# rigidPCB.net
KiCad netlist of a schematic drawn in Altium Designer
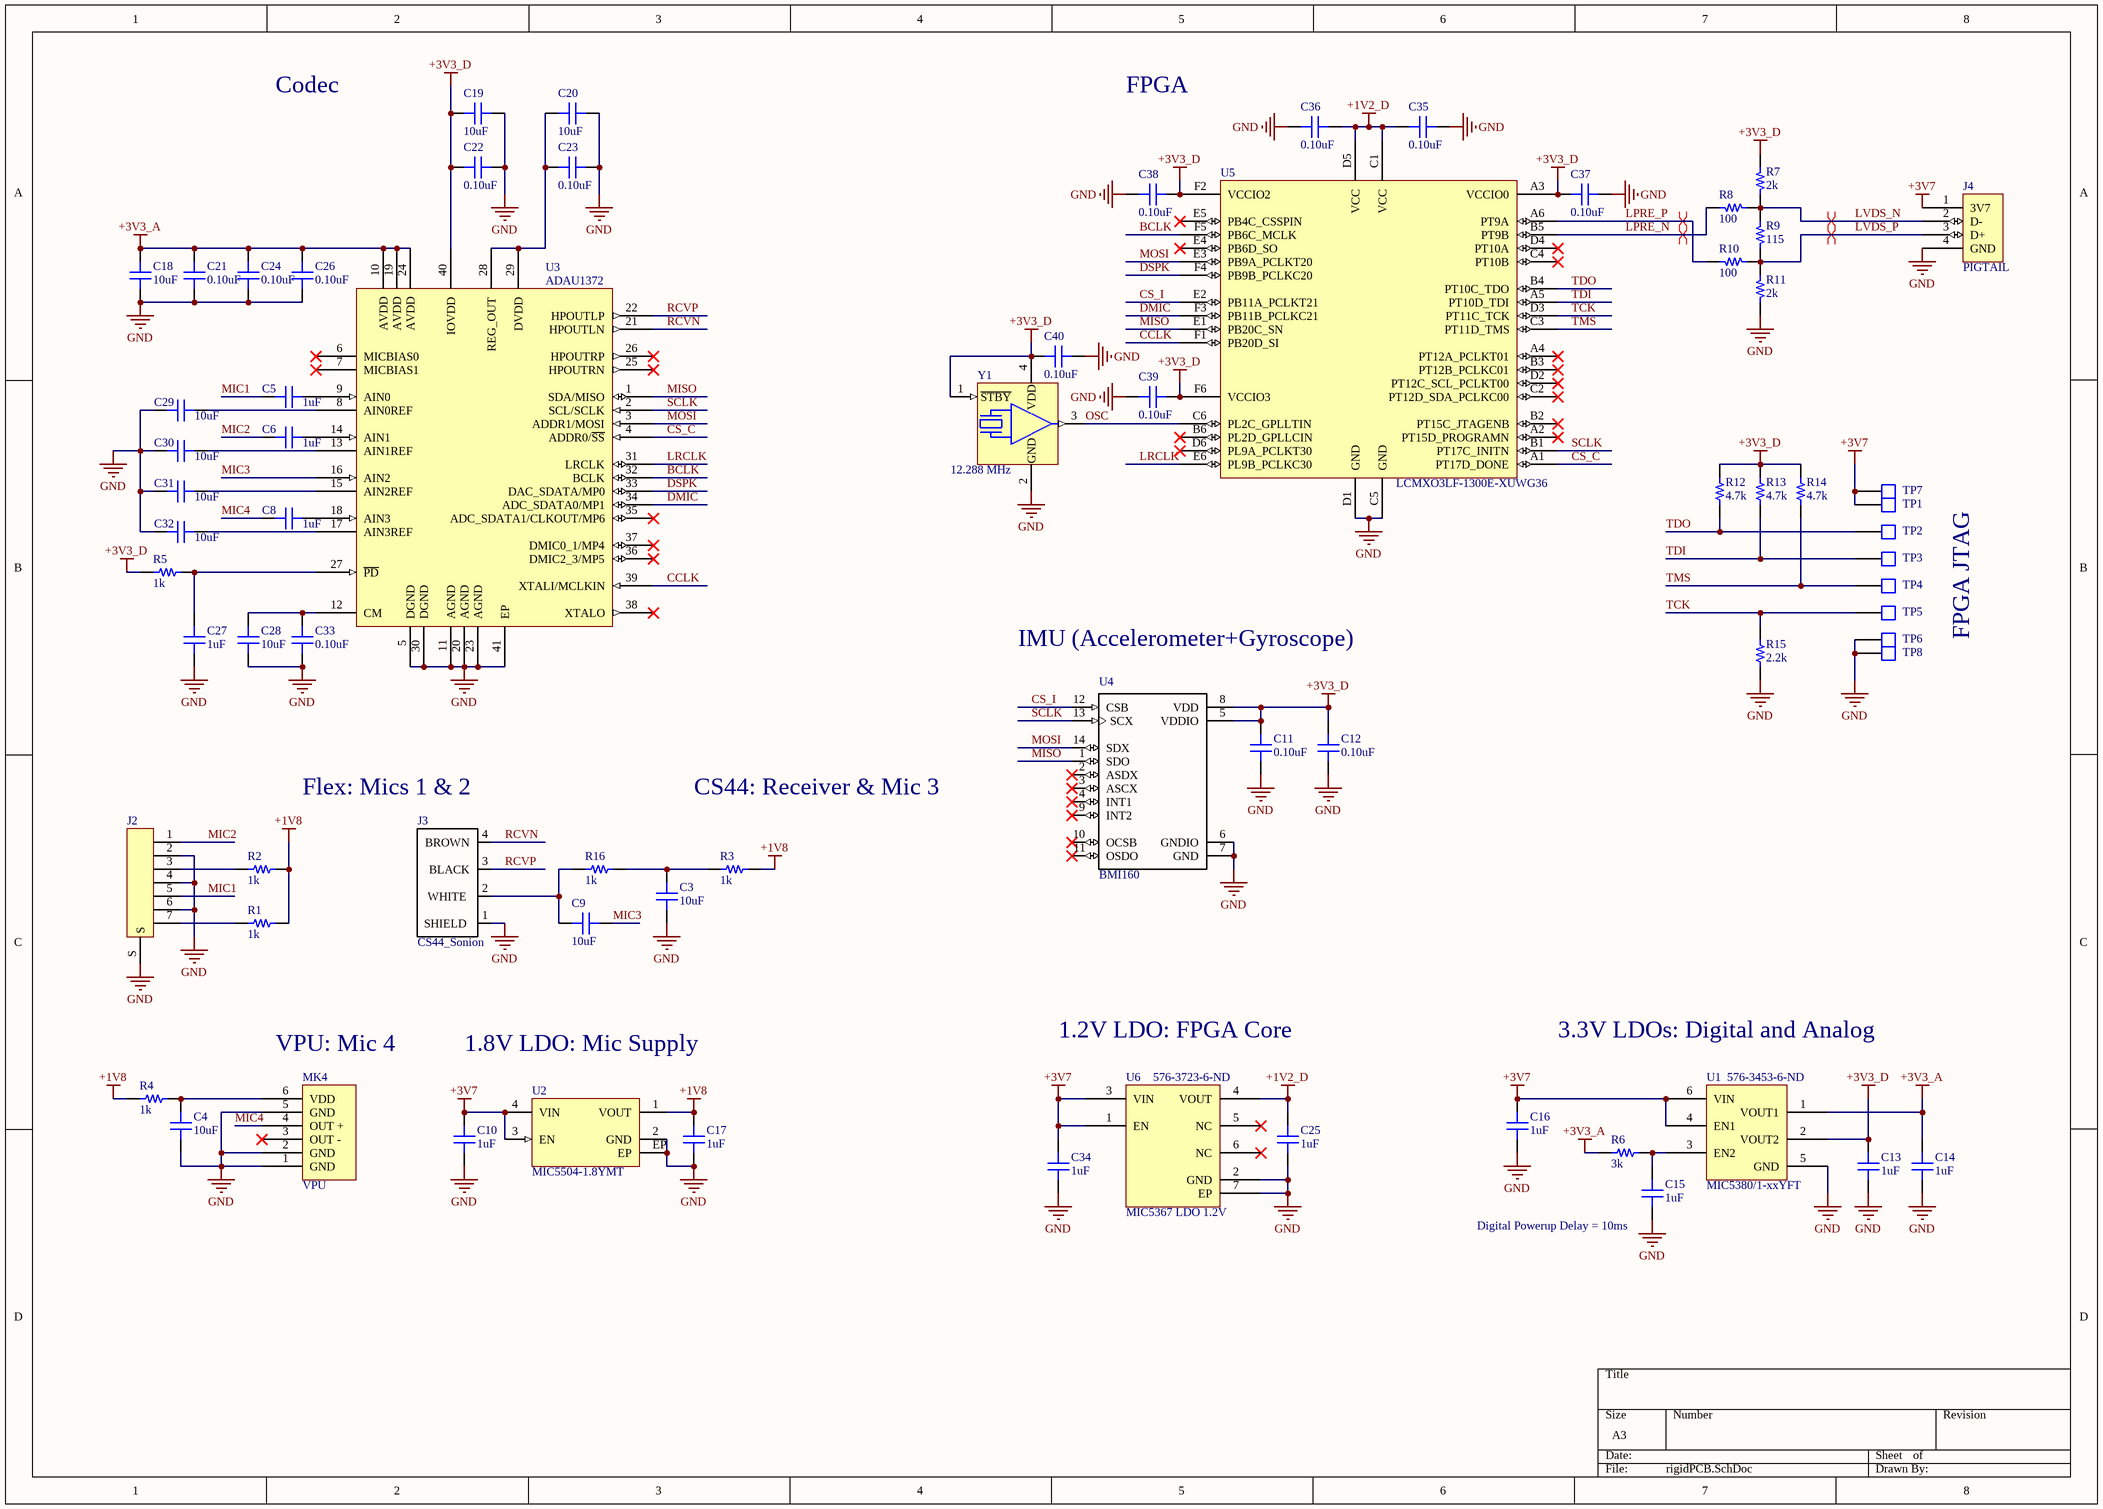
[diagram p0: rigidPCB.SchDoc]

(export (version "E")
  (design (tool "Eeschema 10.0.6"))
  (components
    (comp (ref "C3")
      (value "10uF")
      (footprint "CAP 0402/1005")
      (description "CAP CER 10UF 6.3V X5R 0402")
      (fields
        (field (name "PART NUMBER") "C1005X5R0J106M050BC")
        (field (name "MANUFACTURER") "TDK Corporation")
      )
      (libsource (lib "Celestial Library Database") (part "Capacitor"))
    )
    (comp (ref "C4")
      (value "10uF")
      (footprint "CAP 0402/1005")
      (description "CAP CER 10UF 6.3V X5R 0402")
      (fields
        (field (name "PART NUMBER") "C1005X5R0J106M050BC")
        (field (name "MANUFACTURER") "TDK Corporation")
      )
      (libsource (lib "Celestial Library Database") (part "Capacitor"))
    )
    (comp (ref "C5")
      (value "1uF")
      (footprint "CAP 0201/0603")
      (description "CAP CER 1UF 6.3V X5R 0201")
      (fields (field (name "PART NUMBER") "02016D105MAT2A") (field (name "MANUFACTURER") "AVX Corporation"))
      (libsource (lib "Celestial Library Database") (part "Capacitor"))
    )
    (comp (ref "C6")
      (value "1uF")
      (footprint "CAP 0201/0603")
      (description "CAP CER 1UF 6.3V X5R 0201")
      (fields (field (name "PART NUMBER") "02016D105MAT2A") (field (name "MANUFACTURER") "AVX Corporation"))
      (libsource (lib "Celestial Library Database") (part "Capacitor"))
    )
    (comp (ref "C8")
      (value "1uF")
      (footprint "CAP 0201/0603")
      (description "CAP CER 1UF 6.3V X5R 0201")
      (fields (field (name "PART NUMBER") "02016D105MAT2A") (field (name "MANUFACTURER") "AVX Corporation"))
      (libsource (lib "Celestial Library Database") (part "Capacitor"))
    )
    (comp (ref "C9")
      (value "10uF")
      (footprint "CAP 0402/1005")
      (description "CAP CER 10UF 6.3V X5R 0402")
      (fields
        (field (name "PART NUMBER") "C1005X5R0J106M050BC")
        (field (name "MANUFACTURER") "TDK Corporation")
      )
      (libsource (lib "Celestial Library Database") (part "Capacitor"))
    )
    (comp (ref "C10")
      (value "1uF")
      (footprint "CAP 0201/0603")
      (description "CAP CER 1UF 6.3V X5R 0201")
      (fields (field (name "PART NUMBER") "02016D105MAT2A") (field (name "MANUFACTURER") "AVX Corporation"))
      (libsource (lib "Celestial Library Database") (part "Capacitor"))
    )
    (comp (ref "C11")
      (value "0.10uF")
      (footprint "CAP 0201/0603")
      (description "CAP CER 0.1UF 10V X5R 0201")
      (fields
        (field (name "PART NUMBER") "CL03A104KP3NNNC")
        (field (name "MANUFACTURER") "Samsung Electro-Mechanics America, Inc.")
      )
      (libsource (lib "Celestial Library Database") (part "Capacitor"))
    )
    (comp (ref "C12")
      (value "0.10uF")
      (footprint "CAP 0201/0603")
      (description "CAP CER 0.1UF 10V X5R 0201")
      (fields
        (field (name "PART NUMBER") "CL03A104KP3NNNC")
        (field (name "MANUFACTURER") "Samsung Electro-Mechanics America, Inc.")
      )
      (libsource (lib "Celestial Library Database") (part "Capacitor"))
    )
    (comp (ref "C13")
      (value "1uF")
      (footprint "CAP 0201/0603")
      (description "CAP CER 1UF 6.3V X5R 0201")
      (fields (field (name "PART NUMBER") "02016D105MAT2A") (field (name "MANUFACTURER") "AVX Corporation"))
      (libsource (lib "Celestial Library Database") (part "Capacitor"))
    )
    (comp (ref "C14")
      (value "1uF")
      (footprint "CAP 0201/0603")
      (description "CAP CER 1UF 6.3V X5R 0201")
      (fields (field (name "PART NUMBER") "02016D105MAT2A") (field (name "MANUFACTURER") "AVX Corporation"))
      (libsource (lib "Celestial Library Database") (part "Capacitor"))
    )
    (comp (ref "C15")
      (value "1uF")
      (footprint "CAP 0201/0603")
      (description "CAP CER 1UF 6.3V X5R 0201")
      (fields (field (name "PART NUMBER") "02016D105MAT2A") (field (name "MANUFACTURER") "AVX Corporation"))
      (libsource (lib "Celestial Library Database") (part "Capacitor"))
    )
    (comp (ref "C16")
      (value "1uF")
      (footprint "CAP 0201/0603")
      (description "CAP CER 1UF 6.3V X5R 0201")
      (fields (field (name "PART NUMBER") "02016D105MAT2A") (field (name "MANUFACTURER") "AVX Corporation"))
      (libsource (lib "Celestial Library Database") (part "Capacitor"))
    )
    (comp (ref "C17")
      (value "1uF")
      (footprint "CAP 0201/0603")
      (description "CAP CER 1UF 6.3V X5R 0201")
      (fields (field (name "PART NUMBER") "02016D105MAT2A") (field (name "MANUFACTURER") "AVX Corporation"))
      (libsource (lib "Celestial Library Database") (part "Capacitor"))
    )
    (comp (ref "C18")
      (value "10uF")
      (footprint "CAP 0402/1005")
      (description "CAP CER 10UF 6.3V X5R 0402")
      (fields
        (field (name "PART NUMBER") "C1005X5R0J106M050BC")
        (field (name "MANUFACTURER") "TDK Corporation")
      )
      (libsource (lib "Celestial Library Database") (part "Capacitor"))
    )
    (comp (ref "C19")
      (value "10uF")
      (footprint "CAP 0402/1005")
      (description "CAP CER 10UF 6.3V X5R 0402")
      (fields
        (field (name "PART NUMBER") "C1005X5R0J106M050BC")
        (field (name "MANUFACTURER") "TDK Corporation")
      )
      (libsource (lib "Celestial Library Database") (part "Capacitor"))
    )
    (comp (ref "C20")
      (value "10uF")
      (footprint "CAP 0402/1005")
      (description "CAP CER 10UF 6.3V X5R 0402")
      (fields
        (field (name "PART NUMBER") "C1005X5R0J106M050BC")
        (field (name "MANUFACTURER") "TDK Corporation")
      )
      (libsource (lib "Celestial Library Database") (part "Capacitor"))
    )
    (comp (ref "C21")
      (value "0.10uF")
      (footprint "CAP 0201/0603")
      (description "CAP CER 0.1UF 10V X5R 0201")
      (fields
        (field (name "PART NUMBER") "CL03A104KP3NNNC")
        (field (name "MANUFACTURER") "Samsung Electro-Mechanics America, Inc.")
      )
      (libsource (lib "Celestial Library Database") (part "Capacitor"))
    )
    (comp (ref "C22")
      (value "0.10uF")
      (footprint "CAP 0201/0603")
      (description "CAP CER 0.1UF 10V X5R 0201")
      (fields
        (field (name "PART NUMBER") "CL03A104KP3NNNC")
        (field (name "MANUFACTURER") "Samsung Electro-Mechanics America, Inc.")
      )
      (libsource (lib "Celestial Library Database") (part "Capacitor"))
    )
    (comp (ref "C23")
      (value "0.10uF")
      (footprint "CAP 0201/0603")
      (description "CAP CER 0.1UF 10V X5R 0201")
      (fields
        (field (name "PART NUMBER") "CL03A104KP3NNNC")
        (field (name "MANUFACTURER") "Samsung Electro-Mechanics America, Inc.")
      )
      (libsource (lib "Celestial Library Database") (part "Capacitor"))
    )
    (comp (ref "C24")
      (value "0.10uF")
      (footprint "CAP 0201/0603")
      (description "CAP CER 0.1UF 10V X5R 0201")
      (fields
        (field (name "PART NUMBER") "CL03A104KP3NNNC")
        (field (name "MANUFACTURER") "Samsung Electro-Mechanics America, Inc.")
      )
      (libsource (lib "Celestial Library Database") (part "Capacitor"))
    )
    (comp (ref "C25")
      (value "1uF")
      (footprint "CAP 0201/0603")
      (description "CAP CER 1UF 6.3V X5R 0201")
      (fields (field (name "PART NUMBER") "02016D105MAT2A") (field (name "MANUFACTURER") "AVX Corporation"))
      (libsource (lib "Celestial Library Database") (part "Capacitor"))
    )
    (comp (ref "C26")
      (value "0.10uF")
      (footprint "CAP 0201/0603")
      (description "CAP CER 0.1UF 10V X5R 0201")
      (fields
        (field (name "PART NUMBER") "CL03A104KP3NNNC")
        (field (name "MANUFACTURER") "Samsung Electro-Mechanics America, Inc.")
      )
      (libsource (lib "Celestial Library Database") (part "Capacitor"))
    )
    (comp (ref "C27")
      (value "1uF")
      (footprint "CAP 0201/0603")
      (description "CAP CER 1UF 6.3V X5R 0201")
      (fields (field (name "PART NUMBER") "02016D105MAT2A") (field (name "MANUFACTURER") "AVX Corporation"))
      (libsource (lib "Celestial Library Database") (part "Capacitor"))
    )
    (comp (ref "C28")
      (value "10uF")
      (footprint "CAP 0402/1005")
      (description "CAP CER 10UF 6.3V X5R 0402")
      (fields
        (field (name "PART NUMBER") "C1005X5R0J106M050BC")
        (field (name "MANUFACTURER") "TDK Corporation")
      )
      (libsource (lib "Celestial Library Database") (part "Capacitor"))
    )
    (comp (ref "C29")
      (value "10uF")
      (footprint "CAP 0402/1005")
      (description "CAP CER 10UF 6.3V X5R 0402")
      (fields
        (field (name "PART NUMBER") "C1005X5R0J106M050BC")
        (field (name "MANUFACTURER") "TDK Corporation")
      )
      (libsource (lib "Celestial Library Database") (part "Capacitor"))
    )
    (comp (ref "C30")
      (value "10uF")
      (footprint "CAP 0402/1005")
      (description "CAP CER 10UF 6.3V X5R 0402")
      (fields
        (field (name "PART NUMBER") "C1005X5R0J106M050BC")
        (field (name "MANUFACTURER") "TDK Corporation")
      )
      (libsource (lib "Celestial Library Database") (part "Capacitor"))
    )
    (comp (ref "C31")
      (value "10uF")
      (footprint "CAP 0402/1005")
      (description "CAP CER 10UF 6.3V X5R 0402")
      (fields
        (field (name "PART NUMBER") "C1005X5R0J106M050BC")
        (field (name "MANUFACTURER") "TDK Corporation")
      )
      (libsource (lib "Celestial Library Database") (part "Capacitor"))
    )
    (comp (ref "C32")
      (value "10uF")
      (footprint "CAP 0402/1005")
      (description "CAP CER 10UF 6.3V X5R 0402")
      (fields
        (field (name "PART NUMBER") "C1005X5R0J106M050BC")
        (field (name "MANUFACTURER") "TDK Corporation")
      )
      (libsource (lib "Celestial Library Database") (part "Capacitor"))
    )
    (comp (ref "C33")
      (value "0.10uF")
      (footprint "CAP 0201/0603")
      (description "CAP CER 0.1UF 10V X5R 0201")
      (fields
        (field (name "PART NUMBER") "CL03A104KP3NNNC")
        (field (name "MANUFACTURER") "Samsung Electro-Mechanics America, Inc.")
      )
      (libsource (lib "Celestial Library Database") (part "Capacitor"))
    )
    (comp (ref "C34")
      (value "1uF")
      (footprint "CAP 0201/0603")
      (description "CAP CER 1UF 6.3V X5R 0201")
      (fields (field (name "PART NUMBER") "02016D105MAT2A") (field (name "MANUFACTURER") "AVX Corporation"))
      (libsource (lib "Celestial Library Database") (part "Capacitor"))
    )
    (comp (ref "C35")
      (value "0.10uF")
      (footprint "CAP 0201/0603")
      (description "CAP CER 0.1UF 10V X5R 0201")
      (fields
        (field (name "PART NUMBER") "CL03A104KP3NNNC")
        (field (name "MANUFACTURER") "Samsung Electro-Mechanics America, Inc.")
      )
      (libsource (lib "Celestial Library Database") (part "Capacitor"))
    )
    (comp (ref "C36")
      (value "0.10uF")
      (footprint "CAP 0201/0603")
      (description "CAP CER 0.1UF 10V X5R 0201")
      (fields
        (field (name "PART NUMBER") "CL03A104KP3NNNC")
        (field (name "MANUFACTURER") "Samsung Electro-Mechanics America, Inc.")
      )
      (libsource (lib "Celestial Library Database") (part "Capacitor"))
    )
    (comp (ref "C37")
      (value "0.10uF")
      (footprint "CAP 0201/0603")
      (description "CAP CER 0.1UF 10V X5R 0201")
      (fields
        (field (name "PART NUMBER") "CL03A104KP3NNNC")
        (field (name "MANUFACTURER") "Samsung Electro-Mechanics America, Inc.")
      )
      (libsource (lib "Celestial Library Database") (part "Capacitor"))
    )
    (comp (ref "C38")
      (value "0.10uF")
      (footprint "CAP 0201/0603")
      (description "CAP CER 0.1UF 10V X5R 0201")
      (fields
        (field (name "PART NUMBER") "CL03A104KP3NNNC")
        (field (name "MANUFACTURER") "Samsung Electro-Mechanics America, Inc.")
      )
      (libsource (lib "Celestial Library Database") (part "Capacitor"))
    )
    (comp (ref "C39")
      (value "0.10uF")
      (footprint "CAP 0201/0603")
      (description "CAP CER 0.1UF 10V X5R 0201")
      (fields
        (field (name "PART NUMBER") "CL03A104KP3NNNC")
        (field (name "MANUFACTURER") "Samsung Electro-Mechanics America, Inc.")
      )
      (libsource (lib "Celestial Library Database") (part "Capacitor"))
    )
    (comp (ref "C40")
      (value "0.10uF")
      (footprint "CAP 0201/0603")
      (description "CAP CER 0.1UF 10V X5R 0201")
      (fields
        (field (name "PART NUMBER") "CL03A104KP3NNNC")
        (field (name "MANUFACTURER") "Samsung Electro-Mechanics America, Inc.")
      )
      (libsource (lib "Celestial Library Database") (part "Capacitor"))
    )
    (comp (ref "J2")
      (value "FFC")
      (footprint "HIROSE_FH58M-7S-0.25SHW-99")
      (description "Hirose FH58M-7S-0.25SHW(99) 7-pin Top+Bottom Contact FFC Connector")
      (libsource (lib "OSP_Symbols") (part "HIROSE_FH58M-7S-0.25SHW-99"))
    )
    (comp (ref "J3")
      (value "CS44_Sonion")
      (footprint "CS44_SOCKET_TH - EDGE - SONION")
      (description "4-pin connector. Specify TH vs. SMD")
      (fields (field (name "MANUFACTURER") "Knowles") (field (name "MFGPARTNUMBER") "CS44"))
      (libsource (lib "Mark_Library1") (part "CS44_Sonion"))
    )
    (comp (ref "J4")
      (value "PIGTAIL")
      (footprint "PIGTAIL")
      (libsource (lib "Mark_Library1") (part "PIGTAIL"))
    )
    (comp (ref "MK4") (value "VPU") (footprint "VPU") (libsource (lib "Mark_Library1") (part "VPU")))
    (comp (ref "R1")
      (value "1k")
      (footprint "RES 0201/0603")
      (description "RES SMD 1K OHM 5% 1/20W 0201")
      (fields (field (name "PART NUMBER") "RC0201JR-071KL") (field (name "MANUFACTURER") "Yageo"))
      (libsource (lib "Celestial Library Database") (part "Resistor"))
    )
    (comp (ref "R2")
      (value "1k")
      (footprint "RES 0201/0603")
      (description "RES SMD 1K OHM 5% 1/20W 0201")
      (fields (field (name "PART NUMBER") "RC0201JR-071KL") (field (name "MANUFACTURER") "Yageo"))
      (libsource (lib "Celestial Library Database") (part "Resistor"))
    )
    (comp (ref "R3")
      (value "1k")
      (footprint "RES 0201/0603")
      (description "RES SMD 1K OHM 5% 1/20W 0201")
      (fields (field (name "PART NUMBER") "RC0201JR-071KL") (field (name "MANUFACTURER") "Yageo"))
      (libsource (lib "Celestial Library Database") (part "Resistor"))
    )
    (comp (ref "R4")
      (value "1k")
      (footprint "RES 0201/0603")
      (description "RES SMD 1K OHM 5% 1/20W 0201")
      (fields (field (name "PART NUMBER") "RC0201JR-071KL") (field (name "MANUFACTURER") "Yageo"))
      (libsource (lib "Celestial Library Database") (part "Resistor"))
    )
    (comp (ref "R5")
      (value "1k")
      (footprint "RES 0201/0603")
      (description "RES SMD 1K OHM 5% 1/20W 0201")
      (fields (field (name "PART NUMBER") "RC0201JR-071KL") (field (name "MANUFACTURER") "Yageo"))
      (libsource (lib "Celestial Library Database") (part "Resistor"))
    )
    (comp (ref "R6")
      (value "3k")
      (footprint "RES 0201/0603")
      (description "RES SMD 3K OHM 1% 1/20W 0201")
      (fields (field (name "PART NUMBER") "RC0201FR-073KL") (field (name "MANUFACTURER") "Yageo"))
      (libsource (lib "Celestial Library Database") (part "Resistor"))
    )
    (comp (ref "R7")
      (value "2k")
      (footprint "RES 0201/0603")
      (description "RES SMD 2K OHM 1% 1/20W 0201")
      (fields (field (name "PART NUMBER") "RC0201FR-072KL") (field (name "MANUFACTURER") "Yageo"))
      (libsource (lib "Celestial Library Database") (part "Resistor"))
    )
    (comp (ref "R8")
      (value "100")
      (footprint "RES 0201/0603")
      (description "RES SMD 100 OHM 1% 1/20W 0201")
      (fields
        (field (name "PART NUMBER") "RC0603F101CS")
        (field (name "MANUFACTURER") "Samsung Electro-Mechanics America, Inc.")
      )
      (libsource (lib "Celestial Library Database") (part "Resistor"))
    )
    (comp (ref "R9")
      (value "115")
      (footprint "RES 0201/0603")
      (description "RES SMD 115 OHM 1% 1/20W 0201")
      (fields (field (name "PART NUMBER") "RC0201FR-07115RL") (field (name "MANUFACTURER") "Yageo"))
      (libsource (lib "Celestial Library Database") (part "Resistor"))
    )
    (comp (ref "R10")
      (value "100")
      (footprint "RES 0201/0603")
      (description "RES SMD 100 OHM 1% 1/20W 0201")
      (fields
        (field (name "PART NUMBER") "RC0603F101CS")
        (field (name "MANUFACTURER") "Samsung Electro-Mechanics America, Inc.")
      )
      (libsource (lib "Celestial Library Database") (part "Resistor"))
    )
    (comp (ref "R11")
      (value "2k")
      (footprint "RES 0201/0603")
      (description "RES SMD 2K OHM 1% 1/20W 0201")
      (fields (field (name "PART NUMBER") "RC0201FR-072KL") (field (name "MANUFACTURER") "Yageo"))
      (libsource (lib "Celestial Library Database") (part "Resistor"))
    )
    (comp (ref "R12")
      (value "4.7k")
      (footprint "RES 0201/0603")
      (description "RES SMD 4.7K OHM 1% 1/20W 0201")
      (fields (field (name "PART NUMBER") "RC0201FR-074K7L") (field (name "MANUFACTURER") "Yageo"))
      (libsource (lib "Celestial Library Database") (part "Resistor"))
    )
    (comp (ref "R13")
      (value "4.7k")
      (footprint "RES 0201/0603")
      (description "RES SMD 4.7K OHM 1% 1/20W 0201")
      (fields (field (name "PART NUMBER") "RC0201FR-074K7L") (field (name "MANUFACTURER") "Yageo"))
      (libsource (lib "Celestial Library Database") (part "Resistor"))
    )
    (comp (ref "R14")
      (value "4.7k")
      (footprint "RES 0201/0603")
      (description "RES SMD 4.7K OHM 1% 1/20W 0201")
      (fields (field (name "PART NUMBER") "RC0201FR-074K7L") (field (name "MANUFACTURER") "Yageo"))
      (libsource (lib "Celestial Library Database") (part "Resistor"))
    )
    (comp (ref "R15")
      (value "2.2k")
      (footprint "RES 0201/0603")
      (description "RES SMD 2.2K OHM 1% 1/20W 0201")
      (fields
        (field (name "PART NUMBER") "RC0603F222CS")
        (field (name "MANUFACTURER") "Samsung Electro-Mechanics America, Inc.")
      )
      (libsource (lib "Celestial Library Database") (part "Resistor"))
    )
    (comp (ref "R16")
      (value "1k")
      (footprint "RES 0201/0603")
      (description "RES SMD 1K OHM 5% 1/20W 0201")
      (fields (field (name "PART NUMBER") "RC0201JR-071KL") (field (name "MANUFACTURER") "Yageo"))
      (libsource (lib "Celestial Library Database") (part "Resistor"))
    )
    (comp (ref "TP1")
      (value "TP_SMD_DJB")
      (footprint "TP_SMD_DJB")
      (description "Digital Jellybean Style SMD Test Point")
      (libsource (lib "OSP_Symbols") (part "TP_SMD_DJB"))
    )
    (comp (ref "TP2")
      (value "TP_SMD_DJB")
      (footprint "TP_SMD_DJB")
      (description "Digital Jellybean Style SMD Test Point")
      (libsource (lib "OSP_Symbols") (part "TP_SMD_DJB"))
    )
    (comp (ref "TP3")
      (value "TP_SMD_DJB")
      (footprint "TP_SMD_DJB")
      (description "Digital Jellybean Style SMD Test Point")
      (libsource (lib "OSP_Symbols") (part "TP_SMD_DJB"))
    )
    (comp (ref "TP4")
      (value "TP_SMD_DJB")
      (footprint "TP_SMD_DJB")
      (description "Digital Jellybean Style SMD Test Point")
      (libsource (lib "OSP_Symbols") (part "TP_SMD_DJB"))
    )
    (comp (ref "TP5")
      (value "TP_SMD_DJB")
      (footprint "TP_SMD_DJB")
      (description "Digital Jellybean Style SMD Test Point")
      (libsource (lib "OSP_Symbols") (part "TP_SMD_DJB"))
    )
    (comp (ref "TP6")
      (value "TP_SMD_DJB")
      (footprint "TP_SMD_DJB")
      (description "Digital Jellybean Style SMD Test Point")
      (libsource (lib "OSP_Symbols") (part "TP_SMD_DJB"))
    )
    (comp (ref "TP7")
      (value "TP_SMD_DJB")
      (footprint "TP_SMD_DJB")
      (description "Digital Jellybean Style SMD Test Point")
      (libsource (lib "OSP_Symbols") (part "TP_SMD_DJB"))
    )
    (comp (ref "TP8")
      (value "TP_SMD_DJB")
      (footprint "TP_SMD_DJB")
      (description "Digital Jellybean Style SMD Test Point")
      (libsource (lib "OSP_Symbols") (part "TP_SMD_DJB"))
    )
    (comp (ref "U1")
      (value "MIC5380/1-xxYFT")
      (footprint "06L FCSTSLP")
      (description "LDO 2fixed Outputs")
      (fields (field (name "SUPPLIER PART NUMBER 1") "576-3453-6-ND"))
      (libsource (lib "Mark_Library1") (part "MIC5380/1-xxYFT"))
    )
    (comp (ref "U2")
      (value "MIC5504-1.8YMT")
      (footprint "MICREL_DFN4")
      (description "Micrel MIC5504-1.8YMT 1.8V 300mA LDO")
      (libsource (lib "OSP_Symbols") (part "MICREL_MIC5504-1.8YMT"))
    )
    (comp (ref "U3")
      (value "ADAU1372")
      (footprint "QFN40_LFCSP_WQ_6mmx6mm")
      (description "Analog Devices CODEC")
      (libsource (lib "Mark_Library1") (part "ADAU1372"))
    )
    (comp (ref "U4")
      (value "BMI160")
      (footprint "LGA14R50P5X4_300X250X83")
      (description "BMI160 2.5 x 3 mm Tiaxial Accelerometer / Gyroscope Inertial Measurement Unit")
      (fields (field (name "MF") "Bosch"))
      (libsource (lib "Mark_Library1") (part "BMI160_1"))
    )
    (comp (ref "U5")
      (value "LCMXO3LF-1300E-XUWG36")
      (footprint "BGA36_WLCS_25x25_MachXO3")
      (description "Lattice MachXO3 36-ball 2.5x2.5mm FPGA")
      (libsource (lib "OSP_Symbols") (part "LCMXO3LF-1300E-XUWG36"))
    )
    (comp (ref "U6")
      (value "MIC5367 LDO 1.2V")
      (footprint "LDO 1.2V")
      (fields (field (name "SUPPLIER PART NUMBER 1") "576-3723-6-ND"))
      (libsource (lib "Mark_Library1") (part "MIC5367 LDO 1.2V"))
    )
    (comp (ref "Y1")
      (value "12.288 MHz")
      (footprint "OSC_2.5x2.0mm")
      (description "Microchip 12.288 MHz SMD MEMS Oscillator")
      (libsource (lib "OSP_Symbols") (part "MC_DSC1033DI2-012.2880"))
    )
  )
  (nets
    (net (code "1") (name "+1V2_D") (class "Default")
      (node (ref "C25") (pin "2") (pinfunction "2_2") (pintype "passive"))
      (node (ref "C35") (pin "2") (pinfunction "2_2") (pintype "passive"))
      (node (ref "C36") (pin "1") (pinfunction "1_1") (pintype "passive"))
      (node (ref "U5") (pin "C1") (pinfunction "VCC_C1") (pintype "power_in"))
      (node (ref "U5") (pin "D5") (pinfunction "VCC_D5") (pintype "power_in"))
      (node (ref "U6") (pin "4") (pinfunction "VOUT_4") (pintype "passive"))
    )
    (net (code "2") (name "+1V8") (class "Default")
      (node (ref "C17") (pin "2") (pinfunction "2_2") (pintype "passive"))
      (node (ref "R1") (pin "2") (pinfunction "2_2") (pintype "passive"))
      (node (ref "R2") (pin "2") (pinfunction "2_2") (pintype "passive"))
      (node (ref "R3") (pin "2") (pinfunction "2_2") (pintype "passive"))
      (node (ref "R4") (pin "1") (pinfunction "1_1") (pintype "passive"))
      (node (ref "U2") (pin "1") (pinfunction "VOUT_1") (pintype "power_in"))
    )
    (net (code "3") (name "+3V3_A") (class "Default")
      (node (ref "C14") (pin "2") (pinfunction "2_2") (pintype "passive"))
      (node (ref "C18") (pin "1") (pinfunction "1_1") (pintype "passive"))
      (node (ref "C21") (pin "2") (pinfunction "2_2") (pintype "passive"))
      (node (ref "C24") (pin "2") (pinfunction "2_2") (pintype "passive"))
      (node (ref "C26") (pin "2") (pinfunction "2_2") (pintype "passive"))
      (node (ref "R6") (pin "1") (pinfunction "1_1") (pintype "passive"))
      (node (ref "U1") (pin "1") (pinfunction "VOUT1_1") (pintype "passive"))
      (node (ref "U3") (pin "10") (pinfunction "AVDD_10") (pintype "power_in"))
      (node (ref "U3") (pin "19") (pinfunction "AVDD_19") (pintype "power_in"))
      (node (ref "U3") (pin "24") (pinfunction "AVDD_24") (pintype "power_in"))
    )
    (net (code "4") (name "+3V3_D") (class "Default")
      (node (ref "C11") (pin "2") (pinfunction "2_2") (pintype "passive"))
      (node (ref "C12") (pin "2") (pinfunction "2_2") (pintype "passive"))
      (node (ref "C13") (pin "2") (pinfunction "2_2") (pintype "passive"))
      (node (ref "C19") (pin "2") (pinfunction "2_2") (pintype "passive"))
      (node (ref "C22") (pin "1") (pinfunction "1_1") (pintype "passive"))
      (node (ref "C37") (pin "2") (pinfunction "2_2") (pintype "passive"))
      (node (ref "C38") (pin "1") (pinfunction "1_1") (pintype "passive"))
      (node (ref "C39") (pin "1") (pinfunction "1_1") (pintype "passive"))
      (node (ref "C40") (pin "2") (pinfunction "2_2") (pintype "passive"))
      (node (ref "R12") (pin "2") (pinfunction "2_2") (pintype "passive"))
      (node (ref "R13") (pin "2") (pinfunction "2_2") (pintype "passive"))
      (node (ref "R14") (pin "2") (pinfunction "2_2") (pintype "passive"))
      (node (ref "R5") (pin "1") (pinfunction "1_1") (pintype "passive"))
      (node (ref "R7") (pin "2") (pinfunction "2_2") (pintype "passive"))
      (node (ref "U1") (pin "2") (pinfunction "VOUT2_2") (pintype "passive"))
      (node (ref "U3") (pin "40") (pinfunction "IOVDD_40") (pintype "power_in"))
      (node (ref "U4") (pin "5") (pinfunction "VDDIO_5") (pintype "power_in"))
      (node (ref "U4") (pin "8") (pinfunction "VDD_8") (pintype "power_in"))
      (node (ref "U5") (pin "A3") (pinfunction "VCCIO0_A3") (pintype "power_in"))
      (node (ref "U5") (pin "F2") (pinfunction "VCCIO2_F2") (pintype "power_in"))
      (node (ref "U5") (pin "F6") (pinfunction "VCCIO3_F6") (pintype "power_in"))
      (node (ref "Y1") (pin "1") (pinfunction "~{STBY}_1") (pintype "input"))
      (node (ref "Y1") (pin "4") (pinfunction "VDD_4") (pintype "power_in"))
    )
    (net (code "5") (name "+3V7") (class "Default")
      (node (ref "C10") (pin "2") (pinfunction "2_2") (pintype "passive"))
      (node (ref "C16") (pin "2") (pinfunction "2_2") (pintype "passive"))
      (node (ref "C34") (pin "2") (pinfunction "2_2") (pintype "passive"))
      (node (ref "J4") (pin "1") (pinfunction "3V7_1") (pintype "power_in"))
      (node (ref "TP1") (pin "1") (pintype "passive"))
      (node (ref "TP7") (pin "1") (pintype "passive"))
      (node (ref "U1") (pin "4") (pinfunction "EN1_4") (pintype "passive"))
      (node (ref "U1") (pin "6") (pinfunction "VIN_6") (pintype "passive"))
      (node (ref "U2") (pin "3") (pinfunction "EN_3") (pintype "input"))
      (node (ref "U2") (pin "4") (pinfunction "VIN_4") (pintype "power_in"))
      (node (ref "U6") (pin "1") (pinfunction "EN_1") (pintype "passive"))
      (node (ref "U6") (pin "3") (pinfunction "VIN_3") (pintype "passive"))
    )
    (net (code "6") (name "/BCLK") (class "Default")
      (node (ref "U3") (pin "32") (pinfunction "BCLK_32") (pintype "bidirectional"))
      (node (ref "U5") (pin "F5") (pinfunction "PB6C_MCLK_F5") (pintype "bidirectional"))
    )
    (net (code "7") (name "/CCLK") (class "Default")
      (node (ref "U3") (pin "39") (pinfunction "XTALI/MCLKIN_39") (pintype "input"))
      (node (ref "U5") (pin "F1") (pinfunction "PB20D_SI_F1") (pintype "bidirectional"))
    )
    (net (code "8") (name "/CS_C") (class "Default")
      (node (ref "U3") (pin "4") (pinfunction "ADDR0/~{SS}_4") (pintype "input"))
      (node (ref "U5") (pin "A1") (pinfunction "PT17D_DONE_A1") (pintype "bidirectional"))
    )
    (net (code "9") (name "/CS_I") (class "Default")
      (node (ref "U4") (pin "12") (pinfunction "CSB_12") (pintype "input"))
      (node (ref "U5") (pin "E2") (pinfunction "PB11A_PCLKT21_E2") (pintype "bidirectional"))
    )
    (net (code "10") (name "/DMIC") (class "Default")
      (node (ref "U3") (pin "34") (pinfunction "ADC_SDATA0/MP1_34") (pintype "bidirectional"))
      (node (ref "U5") (pin "F3") (pinfunction "PB11B_PCLKC21_F3") (pintype "bidirectional"))
    )
    (net (code "11") (name "/DSPK") (class "Default")
      (node (ref "U3") (pin "33") (pinfunction "DAC_SDATA/MP0_33") (pintype "bidirectional"))
      (node (ref "U5") (pin "F4") (pinfunction "PB9B_PCLKC20_F4") (pintype "bidirectional"))
    )
    (net (code "12") (name "/LPRE_N") (class "Default")
      (node (ref "R8") (pin "2") (pinfunction "2_2") (pintype "passive"))
      (node (ref "U5") (pin "B5") (pinfunction "PT9B_B5") (pintype "bidirectional"))
    )
    (net (code "13") (name "/LPRE_P") (class "Default")
      (node (ref "R10") (pin "2") (pinfunction "2_2") (pintype "passive"))
      (node (ref "U5") (pin "A6") (pinfunction "PT9A_A6") (pintype "bidirectional"))
    )
    (net (code "14") (name "/LRCLK") (class "Default")
      (node (ref "U3") (pin "31") (pinfunction "LRCLK_31") (pintype "bidirectional"))
      (node (ref "U5") (pin "E6") (pinfunction "PL9B_PCLKC30_E6") (pintype "bidirectional"))
    )
    (net (code "15") (name "/LVDS_N") (class "Default")
      (node (ref "J4") (pin "2") (pinfunction "D-_2") (pintype "bidirectional"))
      (node (ref "R7") (pin "1") (pinfunction "1_1") (pintype "passive"))
      (node (ref "R8") (pin "1") (pinfunction "1_1") (pintype "passive"))
      (node (ref "R9") (pin "2") (pinfunction "2_2") (pintype "passive"))
    )
    (net (code "16") (name "/LVDS_P") (class "Default")
      (node (ref "J4") (pin "3") (pinfunction "D+_3") (pintype "bidirectional"))
      (node (ref "R10") (pin "1") (pinfunction "1_1") (pintype "passive"))
      (node (ref "R11") (pin "2") (pinfunction "2_2") (pintype "passive"))
      (node (ref "R9") (pin "1") (pinfunction "1_1") (pintype "passive"))
    )
    (net (code "17") (name "/MIC1") (class "Default")
      (node (ref "C5") (pin "2") (pinfunction "2_2") (pintype "passive"))
      (node (ref "J2") (pin "5") (pintype "passive"))
    )
    (net (code "18") (name "/MIC2") (class "Default")
      (node (ref "C6") (pin "2") (pinfunction "2_2") (pintype "passive"))
      (node (ref "J2") (pin "1") (pintype "passive"))
    )
    (net (code "19") (name "/MIC3") (class "Default")
      (node (ref "C9") (pin "1") (pinfunction "1_1") (pintype "passive"))
      (node (ref "U3") (pin "16") (pinfunction "AIN2_16") (pintype "input"))
    )
    (net (code "20") (name "/MIC4") (class "Default")
      (node (ref "C8") (pin "2") (pinfunction "2_2") (pintype "passive"))
      (node (ref "MK4") (pin "4") (pinfunction "OUT_+_4") (pintype "passive"))
    )
    (net (code "21") (name "/MISO") (class "Default")
      (node (ref "U3") (pin "1") (pinfunction "SDA/MISO_1") (pintype "bidirectional"))
      (node (ref "U4") (pin "1") (pinfunction "SDO_1") (pintype "bidirectional"))
      (node (ref "U5") (pin "E1") (pinfunction "PB20C_SN_E1") (pintype "bidirectional"))
    )
    (net (code "22") (name "/MOSI") (class "Default")
      (node (ref "U3") (pin "3") (pinfunction "ADDR1/MOSI_3") (pintype "input"))
      (node (ref "U4") (pin "14") (pinfunction "SDX_14") (pintype "bidirectional"))
      (node (ref "U5") (pin "E3") (pinfunction "PB9A_PCLKT20_E3") (pintype "bidirectional"))
    )
    (net (code "23") (name "/OSC") (class "Default")
      (node (ref "U5") (pin "C6") (pinfunction "PL2C_GPLLTIN_C6") (pintype "bidirectional"))
      (node (ref "Y1") (pin "3") (pinfunction "OUT_3") (pintype "output"))
    )
    (net (code "24") (name "/RCVN") (class "Default")
      (node (ref "J3") (pin "4") (pinfunction "BROWN_4") (pintype "passive"))
      (node (ref "U3") (pin "21") (pinfunction "HPOUTLN_21") (pintype "output"))
    )
    (net (code "25") (name "/RCVP") (class "Default")
      (node (ref "J3") (pin "3") (pinfunction "BLACK_3") (pintype "passive"))
      (node (ref "U3") (pin "22") (pinfunction "HPOUTLP_22") (pintype "output"))
    )
    (net (code "26") (name "/SCLK") (class "Default")
      (node (ref "U3") (pin "2") (pinfunction "SCL/SCLK_2") (pintype "input"))
      (node (ref "U4") (pin "13") (pinfunction "SCX_13") (pintype "input"))
      (node (ref "U5") (pin "B1") (pinfunction "PT17C_INITN_B1") (pintype "bidirectional"))
    )
    (net (code "27") (name "/TCK") (class "Default")
      (node (ref "R15") (pin "2") (pinfunction "2_2") (pintype "passive"))
      (node (ref "TP5") (pin "1") (pintype "passive"))
      (node (ref "U5") (pin "D3") (pinfunction "PT11C_TCK_D3") (pintype "bidirectional"))
    )
    (net (code "28") (name "/TDI") (class "Default")
      (node (ref "R13") (pin "1") (pinfunction "1_1") (pintype "passive"))
      (node (ref "TP3") (pin "1") (pintype "passive"))
      (node (ref "U5") (pin "A5") (pinfunction "PT10D_TDI_A5") (pintype "bidirectional"))
    )
    (net (code "29") (name "/TDO") (class "Default")
      (node (ref "R12") (pin "1") (pinfunction "1_1") (pintype "passive"))
      (node (ref "TP2") (pin "1") (pintype "passive"))
      (node (ref "U5") (pin "B4") (pinfunction "PT10C_TDO_B4") (pintype "bidirectional"))
    )
    (net (code "30") (name "/TMS") (class "Default")
      (node (ref "R14") (pin "1") (pinfunction "1_1") (pintype "passive"))
      (node (ref "TP4") (pin "1") (pintype "passive"))
      (node (ref "U5") (pin "C3") (pinfunction "PT11D_TMS_C3") (pintype "bidirectional"))
    )
    (net (code "31") (name "GND") (class "Default")
      (node (ref "C10") (pin "1") (pinfunction "1_1") (pintype "passive"))
      (node (ref "C11") (pin "1") (pinfunction "1_1") (pintype "passive"))
      (node (ref "C12") (pin "1") (pinfunction "1_1") (pintype "passive"))
      (node (ref "C13") (pin "1") (pinfunction "1_1") (pintype "passive"))
      (node (ref "C14") (pin "1") (pinfunction "1_1") (pintype "passive"))
      (node (ref "C15") (pin "1") (pinfunction "1_1") (pintype "passive"))
      (node (ref "C16") (pin "1") (pinfunction "1_1") (pintype "passive"))
      (node (ref "C17") (pin "1") (pinfunction "1_1") (pintype "passive"))
      (node (ref "C18") (pin "2") (pinfunction "2_2") (pintype "passive"))
      (node (ref "C19") (pin "1") (pinfunction "1_1") (pintype "passive"))
      (node (ref "C20") (pin "1") (pinfunction "1_1") (pintype "passive"))
      (node (ref "C21") (pin "1") (pinfunction "1_1") (pintype "passive"))
      (node (ref "C22") (pin "2") (pinfunction "2_2") (pintype "passive"))
      (node (ref "C23") (pin "2") (pinfunction "2_2") (pintype "passive"))
      (node (ref "C24") (pin "1") (pinfunction "1_1") (pintype "passive"))
      (node (ref "C25") (pin "1") (pinfunction "1_1") (pintype "passive"))
      (node (ref "C26") (pin "1") (pinfunction "1_1") (pintype "passive"))
      (node (ref "C27") (pin "1") (pinfunction "1_1") (pintype "passive"))
      (node (ref "C28") (pin "2") (pinfunction "2_2") (pintype "passive"))
      (node (ref "C29") (pin "2") (pinfunction "2_2") (pintype "passive"))
      (node (ref "C3") (pin "1") (pinfunction "1_1") (pintype "passive"))
      (node (ref "C30") (pin "2") (pinfunction "2_2") (pintype "passive"))
      (node (ref "C31") (pin "2") (pinfunction "2_2") (pintype "passive"))
      (node (ref "C32") (pin "2") (pinfunction "2_2") (pintype "passive"))
      (node (ref "C33") (pin "1") (pinfunction "1_1") (pintype "passive"))
      (node (ref "C34") (pin "1") (pinfunction "1_1") (pintype "passive"))
      (node (ref "C35") (pin "1") (pinfunction "1_1") (pintype "passive"))
      (node (ref "C36") (pin "2") (pinfunction "2_2") (pintype "passive"))
      (node (ref "C37") (pin "1") (pinfunction "1_1") (pintype "passive"))
      (node (ref "C38") (pin "2") (pinfunction "2_2") (pintype "passive"))
      (node (ref "C39") (pin "2") (pinfunction "2_2") (pintype "passive"))
      (node (ref "C4") (pin "1") (pinfunction "1_1") (pintype "passive"))
      (node (ref "C40") (pin "1") (pinfunction "1_1") (pintype "passive"))
      (node (ref "J2") (pin "2") (pintype "passive"))
      (node (ref "J2") (pin "4") (pintype "passive"))
      (node (ref "J2") (pin "6") (pintype "passive"))
      (node (ref "J2") (pin "S") (pinfunction "S_S") (pintype "power_in"))
      (node (ref "J3") (pin "1") (pinfunction "SHIELD_1") (pintype "passive"))
      (node (ref "J4") (pin "4") (pinfunction "GND_4") (pintype "power_in"))
      (node (ref "MK4") (pin "1") (pinfunction "GND_1") (pintype "passive"))
      (node (ref "MK4") (pin "2") (pinfunction "GND_2") (pintype "passive"))
      (node (ref "MK4") (pin "5") (pinfunction "GND_5") (pintype "passive"))
      (node (ref "R11") (pin "1") (pinfunction "1_1") (pintype "passive"))
      (node (ref "R15") (pin "1") (pinfunction "1_1") (pintype "passive"))
      (node (ref "TP6") (pin "1") (pintype "passive"))
      (node (ref "TP8") (pin "1") (pintype "passive"))
      (node (ref "U1") (pin "5") (pinfunction "GND_5") (pintype "passive"))
      (node (ref "U2") (pin "2") (pinfunction "GND_2") (pintype "power_in"))
      (node (ref "U2") (pin "EP") (pinfunction "EP_EP") (pintype "power_in"))
      (node (ref "U3") (pin "11") (pinfunction "AGND_11") (pintype "power_in"))
      (node (ref "U3") (pin "20") (pinfunction "AGND_20") (pintype "power_in"))
      (node (ref "U3") (pin "23") (pinfunction "AGND_23") (pintype "power_in"))
      (node (ref "U3") (pin "30") (pinfunction "DGND_30") (pintype "power_in"))
      (node (ref "U3") (pin "41") (pinfunction "EP_41") (pintype "power_in"))
      (node (ref "U3") (pin "5") (pinfunction "DGND_5") (pintype "power_in"))
      (node (ref "U4") (pin "6") (pinfunction "GNDIO_6") (pintype "power_in"))
      (node (ref "U4") (pin "7") (pinfunction "GND_7") (pintype "power_in"))
      (node (ref "U5") (pin "C5") (pinfunction "GND_C5") (pintype "power_in"))
      (node (ref "U5") (pin "D1") (pinfunction "GND_D1") (pintype "power_in"))
      (node (ref "U6") (pin "2") (pinfunction "GND_2") (pintype "passive"))
      (node (ref "U6") (pin "7") (pinfunction "EP_7") (pintype "passive"))
      (node (ref "Y1") (pin "2") (pinfunction "GND_2") (pintype "power_in"))
    )
    (net (code "32") (name "Net-(C3-Pad2)") (class "Default")
      (node (ref "C3") (pin "2") (pinfunction "2_2") (pintype "passive"))
      (node (ref "R16") (pin "2") (pinfunction "2_2") (pintype "passive"))
      (node (ref "R3") (pin "1") (pinfunction "1_1") (pintype "passive"))
    )
    (net (code "33") (name "Net-(J2-Pad3)") (class "Default")
      (node (ref "J2") (pin "3") (pintype "passive"))
      (node (ref "R2") (pin "1") (pinfunction "1_1") (pintype "passive"))
    )
    (net (code "34") (name "Net-(J2-Pad7)") (class "Default")
      (node (ref "J2") (pin "7") (pintype "passive"))
      (node (ref "R1") (pin "1") (pinfunction "1_1") (pintype "passive"))
    )
    (net (code "35") (name "Net-(J3-WHITE)") (class "Default")
      (node (ref "C9") (pin "2") (pinfunction "2_2") (pintype "passive"))
      (node (ref "J3") (pin "2") (pinfunction "WHITE_2") (pintype "passive"))
      (node (ref "R16") (pin "1") (pinfunction "1_1") (pintype "passive"))
    )
    (net (code "36") (name "Net-(MK4-VDD)") (class "Default")
      (node (ref "C4") (pin "2") (pinfunction "2_2") (pintype "passive"))
      (node (ref "MK4") (pin "6") (pinfunction "VDD_6") (pintype "passive"))
      (node (ref "R4") (pin "2") (pinfunction "2_2") (pintype "passive"))
    )
    (net (code "37") (name "Net-(U1-EN2)") (class "Default")
      (node (ref "C15") (pin "2") (pinfunction "2_2") (pintype "passive"))
      (node (ref "R6") (pin "2") (pinfunction "2_2") (pintype "passive"))
      (node (ref "U1") (pin "3") (pinfunction "EN2_3") (pintype "passive"))
    )
    (net (code "38") (name "Net-(U3-AIN0)") (class "Default")
      (node (ref "C5") (pin "1") (pinfunction "1_1") (pintype "passive"))
      (node (ref "U3") (pin "9") (pinfunction "AIN0_9") (pintype "input"))
    )
    (net (code "39") (name "Net-(U3-AIN0REF)") (class "Default")
      (node (ref "C29") (pin "1") (pinfunction "1_1") (pintype "passive"))
      (node (ref "U3") (pin "8") (pinfunction "AIN0REF_8") (pintype "passive"))
    )
    (net (code "40") (name "Net-(U3-AIN1)") (class "Default")
      (node (ref "C6") (pin "1") (pinfunction "1_1") (pintype "passive"))
      (node (ref "U3") (pin "14") (pinfunction "AIN1_14") (pintype "input"))
    )
    (net (code "41") (name "Net-(U3-AIN1REF)") (class "Default")
      (node (ref "C30") (pin "1") (pinfunction "1_1") (pintype "passive"))
      (node (ref "U3") (pin "13") (pinfunction "AIN1REF_13") (pintype "passive"))
    )
    (net (code "42") (name "Net-(U3-AIN2REF)") (class "Default")
      (node (ref "C31") (pin "1") (pinfunction "1_1") (pintype "passive"))
      (node (ref "U3") (pin "15") (pinfunction "AIN2REF_15") (pintype "passive"))
    )
    (net (code "43") (name "Net-(U3-AIN3)") (class "Default")
      (node (ref "C8") (pin "1") (pinfunction "1_1") (pintype "passive"))
      (node (ref "U3") (pin "18") (pinfunction "AIN3_18") (pintype "input"))
    )
    (net (code "44") (name "Net-(U3-AIN3REF)") (class "Default")
      (node (ref "C32") (pin "1") (pinfunction "1_1") (pintype "passive"))
      (node (ref "U3") (pin "17") (pinfunction "AIN3REF_17") (pintype "passive"))
    )
    (net (code "45") (name "Net-(U3-CM)") (class "Default")
      (node (ref "C28") (pin "1") (pinfunction "1_1") (pintype "passive"))
      (node (ref "C33") (pin "2") (pinfunction "2_2") (pintype "passive"))
      (node (ref "U3") (pin "12") (pinfunction "CM_12") (pintype "power_in"))
    )
    (net (code "46") (name "Net-(U3-DVDD)") (class "Default")
      (node (ref "C20") (pin "2") (pinfunction "2_2") (pintype "passive"))
      (node (ref "C23") (pin "1") (pinfunction "1_1") (pintype "passive"))
      (node (ref "U3") (pin "28") (pinfunction "REG_OUT_28") (pintype "power_in"))
      (node (ref "U3") (pin "29") (pinfunction "DVDD_29") (pintype "power_in"))
    )
    (net (code "47") (name "Net-(U3-~{PD})") (class "Default")
      (node (ref "C27") (pin "2") (pinfunction "2_2") (pintype "passive"))
      (node (ref "R5") (pin "2") (pinfunction "2_2") (pintype "passive"))
      (node (ref "U3") (pin "27") (pinfunction "~{PD}_27") (pintype "input"))
    )
    (net (code "48") (name "unconnected-(MK4-OUT_--Pad3)") (class "Default")
      (node (ref "MK4") (pin "3") (pinfunction "OUT_-_3") (pintype "passive+no_connect"))
    )
    (net (code "49") (name "unconnected-(U3-ADC_SDATA1{slash}CLKOUT{slash}MP6-Pad35)") (class "Default")
      (node (ref "U3") (pin "35") (pinfunction "ADC_SDATA1/CLKOUT/MP6_35") (pintype "bidirectional+no_connect"))
    )
    (net (code "50") (name "unconnected-(U3-DMIC0_1{slash}MP4-Pad37)") (class "Default")
      (node (ref "U3") (pin "37") (pinfunction "DMIC0_1/MP4_37") (pintype "bidirectional+no_connect"))
    )
    (net (code "51") (name "unconnected-(U3-DMIC2_3{slash}MP5-Pad36)") (class "Default")
      (node (ref "U3") (pin "36") (pinfunction "DMIC2_3/MP5_36") (pintype "bidirectional+no_connect"))
    )
    (net (code "52") (name "unconnected-(U3-HPOUTRN-Pad25)") (class "Default")
      (node (ref "U3") (pin "25") (pinfunction "HPOUTRN_25") (pintype "output+no_connect"))
    )
    (net (code "53") (name "unconnected-(U3-HPOUTRP-Pad26)") (class "Default")
      (node (ref "U3") (pin "26") (pinfunction "HPOUTRP_26") (pintype "output+no_connect"))
    )
    (net (code "54") (name "unconnected-(U3-MICBIAS0-Pad6)") (class "Default")
      (node (ref "U3") (pin "6") (pinfunction "MICBIAS0_6") (pintype "power_in+no_connect"))
    )
    (net (code "55") (name "unconnected-(U3-MICBIAS1-Pad7)") (class "Default")
      (node (ref "U3") (pin "7") (pinfunction "MICBIAS1_7") (pintype "power_in+no_connect"))
    )
    (net (code "56") (name "unconnected-(U3-XTALO-Pad38)") (class "Default")
      (node (ref "U3") (pin "38") (pinfunction "XTALO_38") (pintype "output+no_connect"))
    )
    (net (code "57") (name "unconnected-(U4-ASCX-Pad3)") (class "Default")
      (node (ref "U4") (pin "3") (pinfunction "ASCX_3") (pintype "bidirectional+no_connect"))
    )
    (net (code "58") (name "unconnected-(U4-ASDX-Pad2)") (class "Default")
      (node (ref "U4") (pin "2") (pinfunction "ASDX_2") (pintype "bidirectional+no_connect"))
    )
    (net (code "59") (name "unconnected-(U4-INT1-Pad4)") (class "Default")
      (node (ref "U4") (pin "4") (pinfunction "INT1_4") (pintype "bidirectional+no_connect"))
    )
    (net (code "60") (name "unconnected-(U4-INT2-Pad9)") (class "Default")
      (node (ref "U4") (pin "9") (pinfunction "INT2_9") (pintype "bidirectional+no_connect"))
    )
    (net (code "61") (name "unconnected-(U4-OCSB-Pad10)") (class "Default")
      (node (ref "U4") (pin "10") (pinfunction "OCSB_10") (pintype "bidirectional+no_connect"))
    )
    (net (code "62") (name "unconnected-(U4-OSDO-Pad11)") (class "Default")
      (node (ref "U4") (pin "11") (pinfunction "OSDO_11") (pintype "bidirectional+no_connect"))
    )
    (net (code "63") (name "unconnected-(U5-PB4C_CSSPIN-PadE5)") (class "Default")
      (node (ref "U5") (pin "E5") (pinfunction "PB4C_CSSPIN_E5") (pintype "bidirectional+no_connect"))
    )
    (net (code "64") (name "unconnected-(U5-PB6D_SO-PadE4)") (class "Default")
      (node (ref "U5") (pin "E4") (pinfunction "PB6D_SO_E4") (pintype "bidirectional+no_connect"))
    )
    (net (code "65") (name "unconnected-(U5-PL2D_GPLLCIN-PadB6)") (class "Default")
      (node (ref "U5") (pin "B6") (pinfunction "PL2D_GPLLCIN_B6") (pintype "bidirectional+no_connect"))
    )
    (net (code "66") (name "unconnected-(U5-PL9A_PCLKT30-PadD6)") (class "Default")
      (node (ref "U5") (pin "D6") (pinfunction "PL9A_PCLKT30_D6") (pintype "bidirectional+no_connect"))
    )
    (net (code "67") (name "unconnected-(U5-PT10A-PadD4)") (class "Default")
      (node (ref "U5") (pin "D4") (pinfunction "PT10A_D4") (pintype "bidirectional+no_connect"))
    )
    (net (code "68") (name "unconnected-(U5-PT10B-PadC4)") (class "Default")
      (node (ref "U5") (pin "C4") (pinfunction "PT10B_C4") (pintype "bidirectional+no_connect"))
    )
    (net (code "69") (name "unconnected-(U5-PT12A_PCLKT01-PadA4)") (class "Default")
      (node (ref "U5") (pin "A4") (pinfunction "PT12A_PCLKT01_A4") (pintype "bidirectional+no_connect"))
    )
    (net (code "70") (name "unconnected-(U5-PT12B_PCLKC01-PadB3)") (class "Default")
      (node (ref "U5") (pin "B3") (pinfunction "PT12B_PCLKC01_B3") (pintype "bidirectional+no_connect"))
    )
    (net (code "71") (name "unconnected-(U5-PT12C_SCL_PCLKT00-PadD2)") (class "Default")
      (node (ref "U5") (pin "D2") (pinfunction "PT12C_SCL_PCLKT00_D2") (pintype "bidirectional+no_connect"))
    )
    (net (code "72") (name "unconnected-(U5-PT12D_SDA_PCLKC00-PadC2)") (class "Default")
      (node (ref "U5") (pin "C2") (pinfunction "PT12D_SDA_PCLKC00_C2") (pintype "bidirectional+no_connect"))
    )
    (net (code "73") (name "unconnected-(U5-PT15C_JTAGENB-PadB2)") (class "Default")
      (node (ref "U5") (pin "B2") (pinfunction "PT15C_JTAGENB_B2") (pintype "bidirectional+no_connect"))
    )
    (net (code "74") (name "unconnected-(U5-PT15D_PROGRAMN-PadA2)") (class "Default")
      (node (ref "U5") (pin "A2") (pinfunction "PT15D_PROGRAMN_A2") (pintype "bidirectional+no_connect"))
    )
    (net (code "75") (name "unconnected-(U6-NC-Pad5)") (class "Default")
      (node (ref "U6") (pin "5") (pinfunction "NC_5") (pintype "passive+no_connect"))
    )
    (net (code "76") (name "unconnected-(U6-NC-Pad6)") (class "Default")
      (node (ref "U6") (pin "6") (pinfunction "NC_6") (pintype "passive+no_connect"))
    )
  )
)
